# puddigDCconverterNotUse.net
KiCad netlist of a schematic drawn in EAGLE
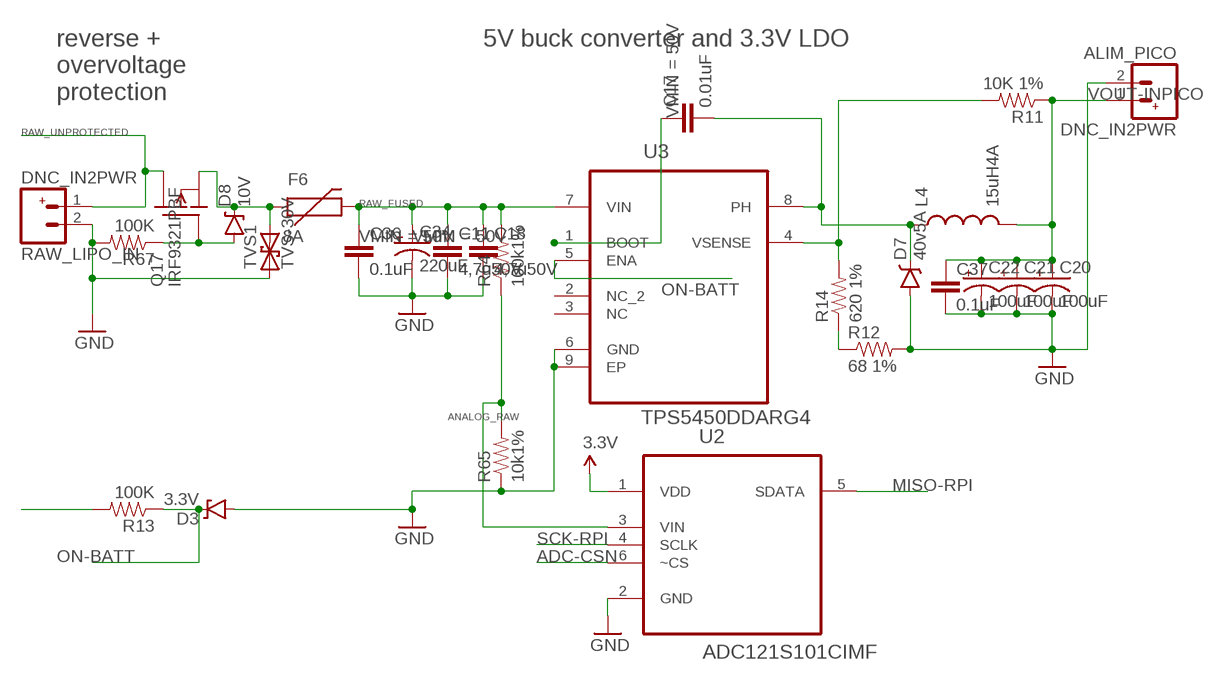
[diagram p0: schematic, sheet 1]

(export (version "E")
  (design (tool "Eeschema 10.0.6"))
  (components
    (comp (ref "ALIM_PICO")
      (value "DNC_IN2PWR")
      (footprint "eagle-import:DNC_IN2_PWR")
      (libsource (lib "eagle-import") (part "DNC_IN2PWR"))
    )
    (comp (ref "C11")
      (value "4,7u50V")
      (footprint "eagle-import:1206")
      (libsource (lib "eagle-import") (part "CAP1206"))
    )
    (comp (ref "C17")
      (value "0.01uF")
      (footprint "eagle-import:C0603")
      (fields (field (name "VMIN") "50V"))
      (libsource (lib "eagle-import") (part "C-EUC0603"))
    )
    (comp (ref "C18")
      (value "4,7u50V")
      (footprint "eagle-import:1206")
      (libsource (lib "eagle-import") (part "CAP1206"))
    )
    (comp (ref "C20")
      (value "100uF")
      (footprint "eagle-import:EIA7343")
      (libsource (lib "eagle-import") (part "100UF-10V-10%(TANT)"))
    )
    (comp (ref "C21")
      (value "100uF")
      (footprint "eagle-import:EIA7343")
      (libsource (lib "eagle-import") (part "100UF-10V-10%(TANT)"))
    )
    (comp (ref "C22")
      (value "100uF")
      (footprint "eagle-import:EIA7343")
      (libsource (lib "eagle-import") (part "100UF-10V-10%(TANT)"))
    )
    (comp (ref "C34")
      (value "220uF")
      (footprint "eagle-import:PANASONIC_E")
      (fields (field (name "VMIN") "50V"))
      (libsource (lib "eagle-import") (part "CAP_POLE"))
    )
    (comp (ref "C36")
      (value "0.1uF")
      (footprint "eagle-import:C0603")
      (fields (field (name "VMIN") "50V"))
      (libsource (lib "eagle-import") (part "C-EUC0603"))
    )
    (comp (ref "C37")
      (value "0.1uF")
      (footprint "eagle-import:C0603")
      (libsource (lib "eagle-import") (part "C-EUC0603"))
    )
    (comp (ref "D3")
      (value "3.3V")
      (footprint "eagle-import:SOD-123")
      (libsource (lib "eagle-import") (part "DIODE-ZENERSOD-123"))
    )
    (comp (ref "D7")
      (value "40v5A")
      (footprint "eagle-import:DO-221")
      (libsource (lib "eagle-import") (part "DIODE_SCHOTKYSMPA"))
    )
    (comp (ref "D8")
      (value "10V")
      (footprint "eagle-import:SOD-123")
      (libsource (lib "eagle-import") (part "DIODE-ZENERSOD-123"))
    )
    (comp (ref "F6")
      (value "8A")
      (footprint "eagle-import:PTC")
      (libsource (lib "eagle-import") (part "PTCPTH"))
    )
    (comp (ref "L4")
      (value "15uH4A")
      (footprint "eagle-import:CDRH125")
      (libsource (lib "eagle-import") (part "INDUCTORPWR"))
    )
    (comp (ref "Q17")
      (value "IRF9321PBF")
      (footprint "eagle-import:SO-8")
      (libsource (lib "eagle-import") (part "IRF9321PBF"))
    )
    (comp (ref "R11")
      (value "10K 1%")
      (footprint "eagle-import:0603-RES")
      (libsource (lib "eagle-import") (part "RESISTOR0603-RES"))
    )
    (comp (ref "R12")
      (value "68 1%")
      (footprint "eagle-import:0603-RES")
      (libsource (lib "eagle-import") (part "RESISTOR0603-RES"))
    )
    (comp (ref "R13")
      (value "100K")
      (footprint "eagle-import:0603-RES")
      (libsource (lib "eagle-import") (part "RESISTOR0603-RES"))
    )
    (comp (ref "R14")
      (value "620 1%")
      (footprint "eagle-import:0603-RES")
      (libsource (lib "eagle-import") (part "RESISTOR0603-RES"))
    )
    (comp (ref "R64")
      (value "100k1%")
      (footprint "eagle-import:0603-RES")
      (libsource (lib "eagle-import") (part "RESISTOR0603-RES"))
    )
    (comp (ref "R65")
      (value "10k1%")
      (footprint "eagle-import:0603-RES")
      (libsource (lib "eagle-import") (part "RESISTOR0603-RES"))
    )
    (comp (ref "R67")
      (value "100K")
      (footprint "eagle-import:0603-RES")
      (libsource (lib "eagle-import") (part "RESISTOR0603-RES"))
    )
    (comp (ref "RAW_LIPO_IN")
      (value "DNC_IN2PWR")
      (footprint "eagle-import:DNC_IN2_PWR")
      (libsource (lib "eagle-import") (part "DNC_IN2PWR"))
    )
    (comp (ref "TVS1")
      (value "TVS-30V")
      (footprint "eagle-import:SMA-DIODE")
      (libsource (lib "eagle-import") (part "TVS"))
    )
    (comp (ref "U2")
      (value "ADC121S101CIMF")
      (footprint "eagle-import:SOT95P284X122-6N")
      (libsource (lib "eagle-import") (part "ADC121S101CIMF"))
    )
    (comp (ref "U3")
      (value "TPS5450DDARG4")
      (footprint "eagle-import:SOIC127P600X170-9N")
      (libsource (lib "eagle-import") (part "TPS5450DDARG4"))
    )
  )
  (nets
    (net (code "1") (name "/ADC-CSN") (class "Default")
      (node (ref "U2") (pin "6") (pinfunction "~{CS}_6") (pintype "input"))
    )
    (net (code "2") (name "/ANALOG_RAW") (class "Default")
      (node (ref "R64") (pin "1") (pinfunction "1_1") (pintype "passive"))
      (node (ref "R65") (pin "2") (pinfunction "2_2") (pintype "passive"))
      (node (ref "U2") (pin "3") (pinfunction "VIN_3") (pintype "input"))
    )
    (net (code "3") (name "/MISO-RPI") (class "Default")
      (node (ref "U2") (pin "5") (pinfunction "SDATA_5") (pintype "output"))
    )
    (net (code "4") (name "/ON-BATT") (class "Default")
      (node (ref "D3") (pin "C") (pinfunction "C_C") (pintype "passive"))
      (node (ref "R13") (pin "1") (pinfunction "1_1") (pintype "passive"))
      (node (ref "U3") (pin "5") (pinfunction "ENA_5") (pintype "input"))
    )
    (net (code "5") (name "/RAW_FUSED") (class "Default")
      (node (ref "C11") (pin "1") (pinfunction "1_1") (pintype "passive"))
      (node (ref "C18") (pin "1") (pinfunction "1_1") (pintype "passive"))
      (node (ref "C34") (pin "+") (pinfunction "+_+") (pintype "passive"))
      (node (ref "C36") (pin "1") (pinfunction "1_1") (pintype "passive"))
      (node (ref "F6") (pin "P$2") (pinfunction "2_P$2") (pintype "bidirectional"))
      (node (ref "R13") (pin "2") (pinfunction "2_2") (pintype "passive"))
      (node (ref "R64") (pin "2") (pinfunction "2_2") (pintype "passive"))
      (node (ref "U3") (pin "7") (pinfunction "VIN_7") (pintype "input"))
    )
    (net (code "6") (name "/RAW_UNPROTECTED") (class "Default")
      (node (ref "Q17") (pin "5") (pinfunction "D_5") (pintype "passive"))
      (node (ref "Q17") (pin "6") (pinfunction "D_6") (pintype "passive"))
      (node (ref "Q17") (pin "7") (pinfunction "D_7") (pintype "passive"))
      (node (ref "Q17") (pin "8") (pinfunction "D_8") (pintype "passive"))
      (node (ref "RAW_LIPO_IN") (pin "1") (pinfunction "+_1") (pintype "passive"))
    )
    (net (code "7") (name "/SCK-RPI") (class "Default")
      (node (ref "U2") (pin "4") (pinfunction "SCLK_4") (pintype "input"))
    )
    (net (code "8") (name "/VOUT-INPICO") (class "Default")
      (node (ref "ALIM_PICO") (pin "1") (pinfunction "+_1") (pintype "passive"))
      (node (ref "C20") (pin "A") (pinfunction "+_A") (pintype "passive"))
      (node (ref "C21") (pin "A") (pinfunction "+_A") (pintype "passive"))
      (node (ref "C22") (pin "A") (pinfunction "+_A") (pintype "passive"))
      (node (ref "C37") (pin "1") (pinfunction "1_1") (pintype "passive"))
      (node (ref "L4") (pin "2") (pinfunction "2_2") (pintype "passive"))
      (node (ref "R11") (pin "1") (pinfunction "1_1") (pintype "passive"))
    )
    (net (code "9") (name "3.3V") (class "Default")
      (node (ref "U2") (pin "1") (pinfunction "VDD_1") (pintype "power_in"))
    )
    (net (code "10") (name "GND") (class "Default")
      (node (ref "ALIM_PICO") (pin "2") (pinfunction "-_2") (pintype "passive"))
      (node (ref "C11") (pin "2") (pinfunction "2_2") (pintype "passive"))
      (node (ref "C18") (pin "2") (pinfunction "2_2") (pintype "passive"))
      (node (ref "C20") (pin "C") (pinfunction "-_C") (pintype "passive"))
      (node (ref "C21") (pin "C") (pinfunction "-_C") (pintype "passive"))
      (node (ref "C22") (pin "C") (pinfunction "-_C") (pintype "passive"))
      (node (ref "C34") (pin "-") (pinfunction "-_-") (pintype "passive"))
      (node (ref "C36") (pin "2") (pinfunction "2_2") (pintype "passive"))
      (node (ref "C37") (pin "2") (pinfunction "2_2") (pintype "passive"))
      (node (ref "D3") (pin "A") (pinfunction "A_A") (pintype "passive"))
      (node (ref "D7") (pin "A") (pinfunction "A_A") (pintype "passive"))
      (node (ref "R12") (pin "2") (pinfunction "2_2") (pintype "passive"))
      (node (ref "R65") (pin "1") (pinfunction "1_1") (pintype "passive"))
      (node (ref "R67") (pin "2") (pinfunction "2_2") (pintype "passive"))
      (node (ref "RAW_LIPO_IN") (pin "2") (pinfunction "-_2") (pintype "passive"))
      (node (ref "TVS1") (pin "A") (pinfunction "1_A") (pintype "passive"))
      (node (ref "U2") (pin "2") (pinfunction "GND_2") (pintype "passive"))
      (node (ref "U3") (pin "6") (pinfunction "GND_6") (pintype "passive"))
      (node (ref "U3") (pin "9") (pinfunction "EP_9") (pintype "passive"))
    )
    (net (code "11") (name "Net-(F6-1)") (class "Default")
      (node (ref "D8") (pin "C") (pinfunction "C_C") (pintype "passive"))
      (node (ref "F6") (pin "P$1MOV") (pinfunction "1_P$1MOV") (pintype "bidirectional"))
      (node (ref "Q17") (pin "1") (pinfunction "S_1") (pintype "passive"))
      (node (ref "Q17") (pin "2") (pinfunction "S_2") (pintype "passive"))
      (node (ref "Q17") (pin "3") (pinfunction "S_3") (pintype "passive"))
      (node (ref "TVS1") (pin "C") (pinfunction "2_C") (pintype "passive"))
    )
    (net (code "12") (name "Net-(Q17-G)") (class "Default")
      (node (ref "D8") (pin "A") (pinfunction "A_A") (pintype "passive"))
      (node (ref "Q17") (pin "4") (pinfunction "G_4") (pintype "passive"))
      (node (ref "R67") (pin "1") (pinfunction "1_1") (pintype "passive"))
    )
    (net (code "13") (name "Net-(R12-Pad1)") (class "Default")
      (node (ref "R12") (pin "1") (pinfunction "1_1") (pintype "passive"))
      (node (ref "R14") (pin "1") (pinfunction "1_1") (pintype "passive"))
    )
    (net (code "14") (name "Net-(U3-BOOT)") (class "Default")
      (node (ref "C17") (pin "1") (pinfunction "1_1") (pintype "passive"))
      (node (ref "U3") (pin "1") (pinfunction "BOOT_1") (pintype "passive"))
    )
    (net (code "15") (name "Net-(U3-PH)") (class "Default")
      (node (ref "C17") (pin "2") (pinfunction "2_2") (pintype "passive"))
      (node (ref "D7") (pin "C") (pinfunction "C_C") (pintype "passive"))
      (node (ref "L4") (pin "1") (pinfunction "1_1") (pintype "passive"))
      (node (ref "U3") (pin "8") (pinfunction "PH_8") (pintype "output"))
    )
    (net (code "16") (name "Net-(U3-VSENSE)") (class "Default")
      (node (ref "R11") (pin "2") (pinfunction "2_2") (pintype "passive"))
      (node (ref "R14") (pin "2") (pinfunction "2_2") (pintype "passive"))
      (node (ref "U3") (pin "4") (pinfunction "VSENSE_4") (pintype "output"))
    )
    (net (code "17") (name "unconnected-(U3-NC-Pad3)") (class "Default")
      (node (ref "U3") (pin "3") (pinfunction "NC_3") (pintype "no_connect"))
    )
    (net (code "18") (name "unconnected-(U3-NC_2-Pad2)") (class "Default")
      (node (ref "U3") (pin "2") (pinfunction "NC_2_2") (pintype "no_connect"))
    )
  )
)
